# Autonomous_Rover.net
KiCad netlist of a schematic drawn in EAGLE
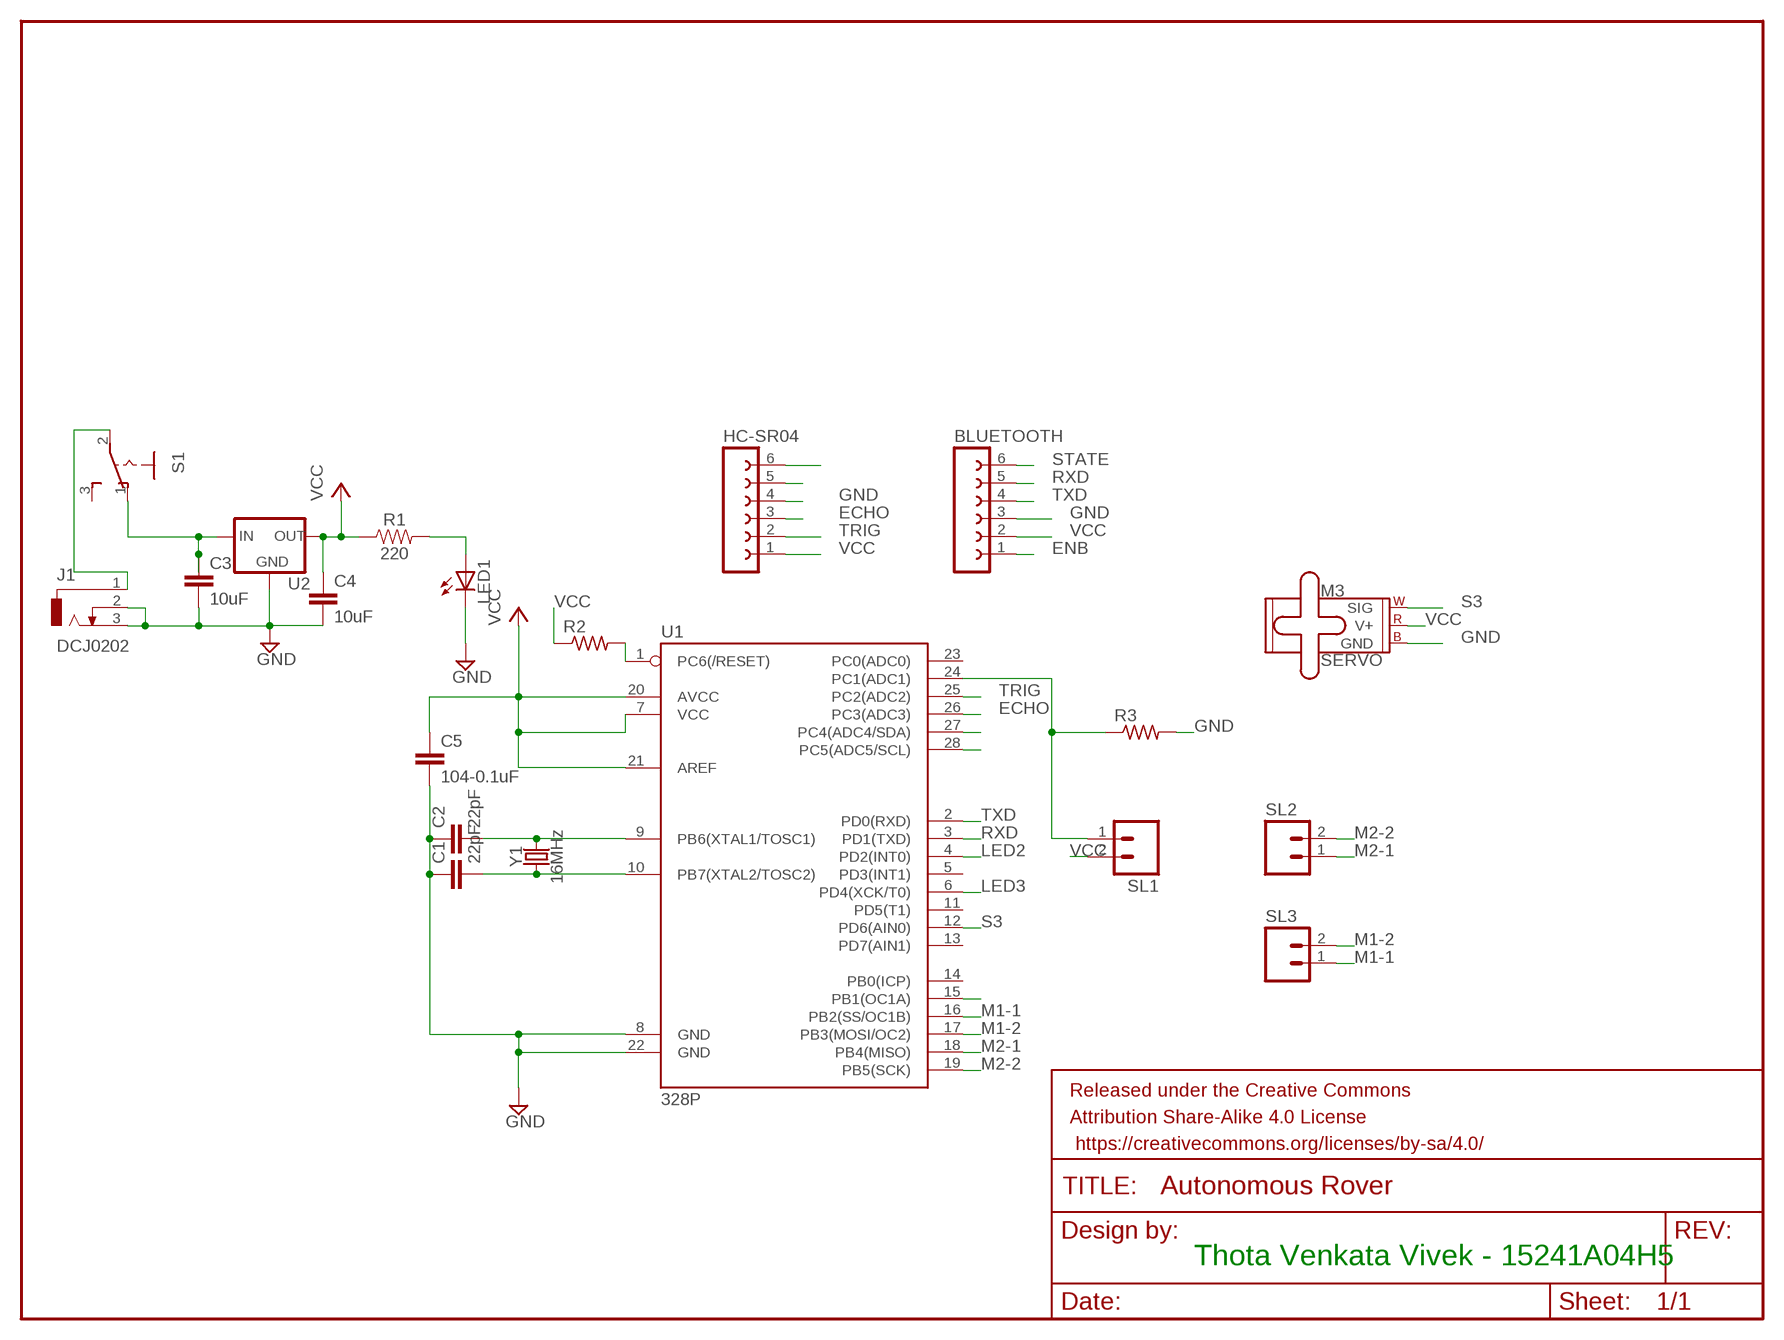
[diagram p0: schematic, sheet 1]

(export (version "E")
  (design (tool "Eeschema 10.0.6"))
  (components
    (comp (ref "BLUETOOTH")
      (value "FE06-1")
      (footprint "eagle-import:FE06")
      (libsource (lib "eagle-import") (part "FE06-1"))
    )
    (comp (ref "C1")
      (value "22pF")
      (footprint "eagle-import:C2.5-3")
      (libsource (lib "eagle-import") (part "C2,5-3"))
    )
    (comp (ref "C2")
      (value "22pF")
      (footprint "eagle-import:C2.5-3")
      (libsource (lib "eagle-import") (part "C2,5-3"))
    )
    (comp (ref "C3")
      (value "10uF")
      (footprint "eagle-import:C2.5-3")
      (libsource (lib "eagle-import") (part "C2,5-3"))
    )
    (comp (ref "C4")
      (value "10uF")
      (footprint "eagle-import:C2.5-3")
      (libsource (lib "eagle-import") (part "C2,5-3"))
    )
    (comp (ref "C5")
      (value "104-0.1uF")
      (footprint "eagle-import:C2.5-3")
      (libsource (lib "eagle-import") (part "C2,5-3"))
    )
    (comp (ref "FRAME1")
      (value "FRAME-LETTER")
      (footprint "eagle-import:CREATIVE_COMMONS")
      (libsource (lib "eagle-import") (part "FRAME-LETTER"))
    )
    (comp (ref "HC-SR04")
      (value "FE06-1")
      (footprint "eagle-import:FE06")
      (libsource (lib "eagle-import") (part "FE06-1"))
    )
    (comp (ref "J1")
      (value "DCJ0202")
      (footprint "eagle-import:DCJ0202")
      (libsource (lib "eagle-import") (part "DCJ0202"))
    )
    (comp (ref "LED1")
      (value "LED3MM")
      (footprint "eagle-import:LED3MM")
      (libsource (lib "eagle-import") (part "LED3MM"))
    )
    (comp (ref "M3")
      (value "SERVO")
      (footprint "eagle-import:1X03")
      (libsource (lib "eagle-import") (part "SERVO"))
    )
    (comp (ref "R1")
      (value "220")
      (footprint "eagle-import:AXIAL-0.3")
      (libsource (lib "eagle-import") (part "10KOHM-HORIZ-1/4W-5%"))
    )
    (comp (ref "R2")
      (value "R-US_0204/7")
      (footprint "eagle-import:0204_7")
      (libsource (lib "eagle-import") (part "R-US_0204/7"))
    )
    (comp (ref "R3")
      (value "R-US_0204/7")
      (footprint "eagle-import:0204_7")
      (libsource (lib "eagle-import") (part "R-US_0204/7"))
    )
    (comp (ref "S1")
      (value "255SB")
      (footprint "eagle-import:255SB")
      (libsource (lib "eagle-import") (part "255SB"))
    )
    (comp (ref "SL1")
      (value "M02")
      (footprint "eagle-import:02P")
      (libsource (lib "eagle-import") (part "M02"))
    )
    (comp (ref "SL2")
      (value "M02")
      (footprint "eagle-import:02P")
      (libsource (lib "eagle-import") (part "M02"))
    )
    (comp (ref "SL3")
      (value "M02")
      (footprint "eagle-import:02P")
      (libsource (lib "eagle-import") (part "M02"))
    )
    (comp (ref "U1")
      (value "328P")
      (footprint "eagle-import:DIP28")
      (libsource (lib "eagle-import") (part "ATMEGA328P_PDIP"))
    )
    (comp (ref "U2")
      (value "V_REG_78XX-TO-220")
      (footprint "eagle-import:TO-220-ALT")
      (libsource (lib "eagle-import") (part "V_REG_78XX-TO-220"))
    )
    (comp (ref "Y1")
      (value "16MHz")
      (footprint "eagle-import:HC49US")
      (libsource (lib "eagle-import") (part "CRYSTAL-16MHZPTH-HC49US"))
    )
  )
  (nets
    (net (code "1") (name "/ECHO") (class "Default")
      (node (ref "HC-SR04") (pin "3") (pinfunction "3_3") (pintype "passive"))
      (node (ref "U1") (pin "26") (pinfunction "PC3(ADC3)_26") (pintype "bidirectional"))
    )
    (net (code "2") (name "/ENB") (class "Default")
      (node (ref "BLUETOOTH") (pin "1") (pinfunction "1_1") (pintype "passive"))
    )
    (net (code "3") (name "/LED2") (class "Default")
      (node (ref "U1") (pin "4") (pinfunction "PD2(INT0)_4") (pintype "bidirectional"))
    )
    (net (code "4") (name "/LED3") (class "Default")
      (node (ref "HC-SR04") (pin "5") (pinfunction "5_5") (pintype "passive"))
      (node (ref "U1") (pin "6") (pinfunction "PD4(XCK/T0)_6") (pintype "bidirectional"))
    )
    (net (code "5") (name "/M1-1") (class "Default")
      (node (ref "SL3") (pin "1") (pinfunction "1_1") (pintype "passive"))
      (node (ref "U1") (pin "16") (pinfunction "PB2(SS/OC1B)_16") (pintype "bidirectional"))
    )
    (net (code "6") (name "/M1-2") (class "Default")
      (node (ref "SL3") (pin "2") (pinfunction "2_2") (pintype "passive"))
      (node (ref "U1") (pin "17") (pinfunction "PB3(MOSI/OC2)_17") (pintype "bidirectional"))
    )
    (net (code "7") (name "/M2-1") (class "Default")
      (node (ref "SL2") (pin "1") (pinfunction "1_1") (pintype "passive"))
      (node (ref "U1") (pin "18") (pinfunction "PB4(MISO)_18") (pintype "bidirectional"))
    )
    (net (code "8") (name "/M2-2") (class "Default")
      (node (ref "SL2") (pin "2") (pinfunction "2_2") (pintype "passive"))
      (node (ref "U1") (pin "19") (pinfunction "PB5(SCK)_19") (pintype "bidirectional"))
    )
    (net (code "9") (name "/RXD") (class "Default")
      (node (ref "BLUETOOTH") (pin "5") (pinfunction "5_5") (pintype "passive"))
      (node (ref "U1") (pin "3") (pinfunction "PD1(TXD)_3") (pintype "bidirectional"))
    )
    (net (code "10") (name "/S3") (class "Default")
      (node (ref "M3") (pin "1") (pinfunction "SIG_1") (pintype "bidirectional"))
      (node (ref "U1") (pin "12") (pinfunction "PD6(AIN0)_12") (pintype "bidirectional"))
    )
    (net (code "11") (name "/STATE") (class "Default")
      (node (ref "BLUETOOTH") (pin "6") (pinfunction "6_6") (pintype "passive"))
    )
    (net (code "12") (name "/TRIG") (class "Default")
      (node (ref "HC-SR04") (pin "2") (pinfunction "2_2") (pintype "passive"))
      (node (ref "U1") (pin "25") (pinfunction "PC2(ADC2)_25") (pintype "bidirectional"))
    )
    (net (code "13") (name "/TXD") (class "Default")
      (node (ref "BLUETOOTH") (pin "4") (pinfunction "4_4") (pintype "passive"))
      (node (ref "U1") (pin "2") (pinfunction "PD0(RXD)_2") (pintype "bidirectional"))
    )
    (net (code "14") (name "GND") (class "Default")
      (node (ref "BLUETOOTH") (pin "3") (pinfunction "3_3") (pintype "passive"))
      (node (ref "C1") (pin "1") (pinfunction "1_1") (pintype "passive"))
      (node (ref "C2") (pin "1") (pinfunction "1_1") (pintype "passive"))
      (node (ref "C3") (pin "2") (pinfunction "2_2") (pintype "passive"))
      (node (ref "C4") (pin "2") (pinfunction "2_2") (pintype "passive"))
      (node (ref "C5") (pin "2") (pinfunction "2_2") (pintype "passive"))
      (node (ref "HC-SR04") (pin "4") (pinfunction "4_4") (pintype "passive"))
      (node (ref "HC-SR04") (pin "6") (pinfunction "6_6") (pintype "passive"))
      (node (ref "J1") (pin "2") (pinfunction "2_2") (pintype "passive"))
      (node (ref "J1") (pin "3") (pinfunction "3_3") (pintype "passive"))
      (node (ref "LED1") (pin "K") (pinfunction "C_K") (pintype "passive"))
      (node (ref "M3") (pin "3") (pinfunction "GND_3") (pintype "bidirectional"))
      (node (ref "R3") (pin "2") (pinfunction "2_2") (pintype "passive"))
      (node (ref "U1") (pin "22") (pinfunction "GND_22") (pintype "bidirectional"))
      (node (ref "U1") (pin "8") (pinfunction "GND_8") (pintype "bidirectional"))
      (node (ref "U2") (pin "GND") (pinfunction "GND_GND") (pintype "input"))
    )
    (net (code "15") (name "Net-(R1-2)") (class "Default")
      (node (ref "LED1") (pin "A") (pinfunction "A_A") (pintype "passive"))
      (node (ref "R1") (pin "P$2") (pinfunction "2_P$2") (pintype "passive"))
    )
    (net (code "16") (name "Net-(S1-O)") (class "Default")
      (node (ref "C3") (pin "1") (pinfunction "1_1") (pintype "passive"))
      (node (ref "S1") (pin "1") (pinfunction "O_1") (pintype "passive"))
      (node (ref "U2") (pin "IN") (pinfunction "IN_IN") (pintype "input"))
    )
    (net (code "17") (name "Net-(S1-P)") (class "Default")
      (node (ref "J1") (pin "1") (pinfunction "1_1") (pintype "passive"))
      (node (ref "S1") (pin "2") (pinfunction "P_2") (pintype "passive"))
    )
    (net (code "18") (name "Net-(U1-PB6(XTAL1{slash}TOSC1))") (class "Default")
      (node (ref "C2") (pin "2") (pinfunction "2_2") (pintype "passive"))
      (node (ref "U1") (pin "9") (pinfunction "PB6(XTAL1/TOSC1)_9") (pintype "bidirectional"))
      (node (ref "Y1") (pin "2") (pinfunction "2_2") (pintype "passive"))
    )
    (net (code "19") (name "Net-(U1-PB7(XTAL2{slash}TOSC2))") (class "Default")
      (node (ref "C1") (pin "2") (pinfunction "2_2") (pintype "passive"))
      (node (ref "U1") (pin "10") (pinfunction "PB7(XTAL2/TOSC2)_10") (pintype "bidirectional"))
      (node (ref "Y1") (pin "1") (pinfunction "1_1") (pintype "passive"))
    )
    (net (code "20") (name "Net-(U1-PC1(ADC1))") (class "Default")
      (node (ref "R3") (pin "1") (pinfunction "1_1") (pintype "passive"))
      (node (ref "SL1") (pin "1") (pinfunction "1_1") (pintype "passive"))
      (node (ref "U1") (pin "24") (pinfunction "PC1(ADC1)_24") (pintype "bidirectional"))
    )
    (net (code "21") (name "Net-(U1-PC6({slash}RESET))") (class "Default")
      (node (ref "R2") (pin "2") (pinfunction "2_2") (pintype "passive"))
      (node (ref "U1") (pin "1") (pinfunction "PC6(/RESET)_1") (pintype "bidirectional"))
    )
    (net (code "22") (name "VCC") (class "Default")
      (node (ref "BLUETOOTH") (pin "2") (pinfunction "2_2") (pintype "passive"))
      (node (ref "C4") (pin "1") (pinfunction "1_1") (pintype "passive"))
      (node (ref "C5") (pin "1") (pinfunction "1_1") (pintype "passive"))
      (node (ref "HC-SR04") (pin "1") (pinfunction "1_1") (pintype "passive"))
      (node (ref "M3") (pin "2") (pinfunction "V+_2") (pintype "bidirectional"))
      (node (ref "R1") (pin "P$1") (pinfunction "1_P$1") (pintype "passive"))
      (node (ref "R2") (pin "1") (pinfunction "1_1") (pintype "passive"))
      (node (ref "SL1") (pin "2") (pinfunction "2_2") (pintype "passive"))
      (node (ref "U1") (pin "20") (pinfunction "AVCC_20") (pintype "bidirectional"))
      (node (ref "U1") (pin "21") (pinfunction "AREF_21") (pintype "bidirectional"))
      (node (ref "U1") (pin "7") (pinfunction "VCC_7") (pintype "bidirectional"))
      (node (ref "U2") (pin "OUT") (pinfunction "OUT_OUT") (pintype "passive"))
    )
    (net (code "23") (name "unconnected-(S1-S-Pad3)") (class "Default")
      (node (ref "S1") (pin "3") (pinfunction "S_3") (pintype "passive"))
    )
    (net (code "24") (name "unconnected-(U1-PB0(ICP)-Pad14)") (class "Default")
      (node (ref "U1") (pin "14") (pinfunction "PB0(ICP)_14") (pintype "bidirectional"))
    )
    (net (code "25") (name "unconnected-(U1-PB1(OC1A)-Pad15)") (class "Default")
      (node (ref "U1") (pin "15") (pinfunction "PB1(OC1A)_15") (pintype "bidirectional"))
    )
    (net (code "26") (name "unconnected-(U1-PC0(ADC0)-Pad23)") (class "Default")
      (node (ref "U1") (pin "23") (pinfunction "PC0(ADC0)_23") (pintype "bidirectional"))
    )
    (net (code "27") (name "unconnected-(U1-PC4(ADC4{slash}SDA)-Pad27)") (class "Default")
      (node (ref "U1") (pin "27") (pinfunction "PC4(ADC4/SDA)_27") (pintype "bidirectional"))
    )
    (net (code "28") (name "unconnected-(U1-PC5(ADC5{slash}SCL)-Pad28)") (class "Default")
      (node (ref "U1") (pin "28") (pinfunction "PC5(ADC5/SCL)_28") (pintype "bidirectional"))
    )
    (net (code "29") (name "unconnected-(U1-PD3(INT1)-Pad5)") (class "Default")
      (node (ref "U1") (pin "5") (pinfunction "PD3(INT1)_5") (pintype "bidirectional"))
    )
    (net (code "30") (name "unconnected-(U1-PD5(T1)-Pad11)") (class "Default")
      (node (ref "U1") (pin "11") (pinfunction "PD5(T1)_11") (pintype "bidirectional"))
    )
    (net (code "31") (name "unconnected-(U1-PD7(AIN1)-Pad13)") (class "Default")
      (node (ref "U1") (pin "13") (pinfunction "PD7(AIN1)_13") (pintype "bidirectional"))
    )
  )
)
